# CDTV-adaptor-ATX_1_1.net
KiCad netlist of a schematic drawn in EAGLE
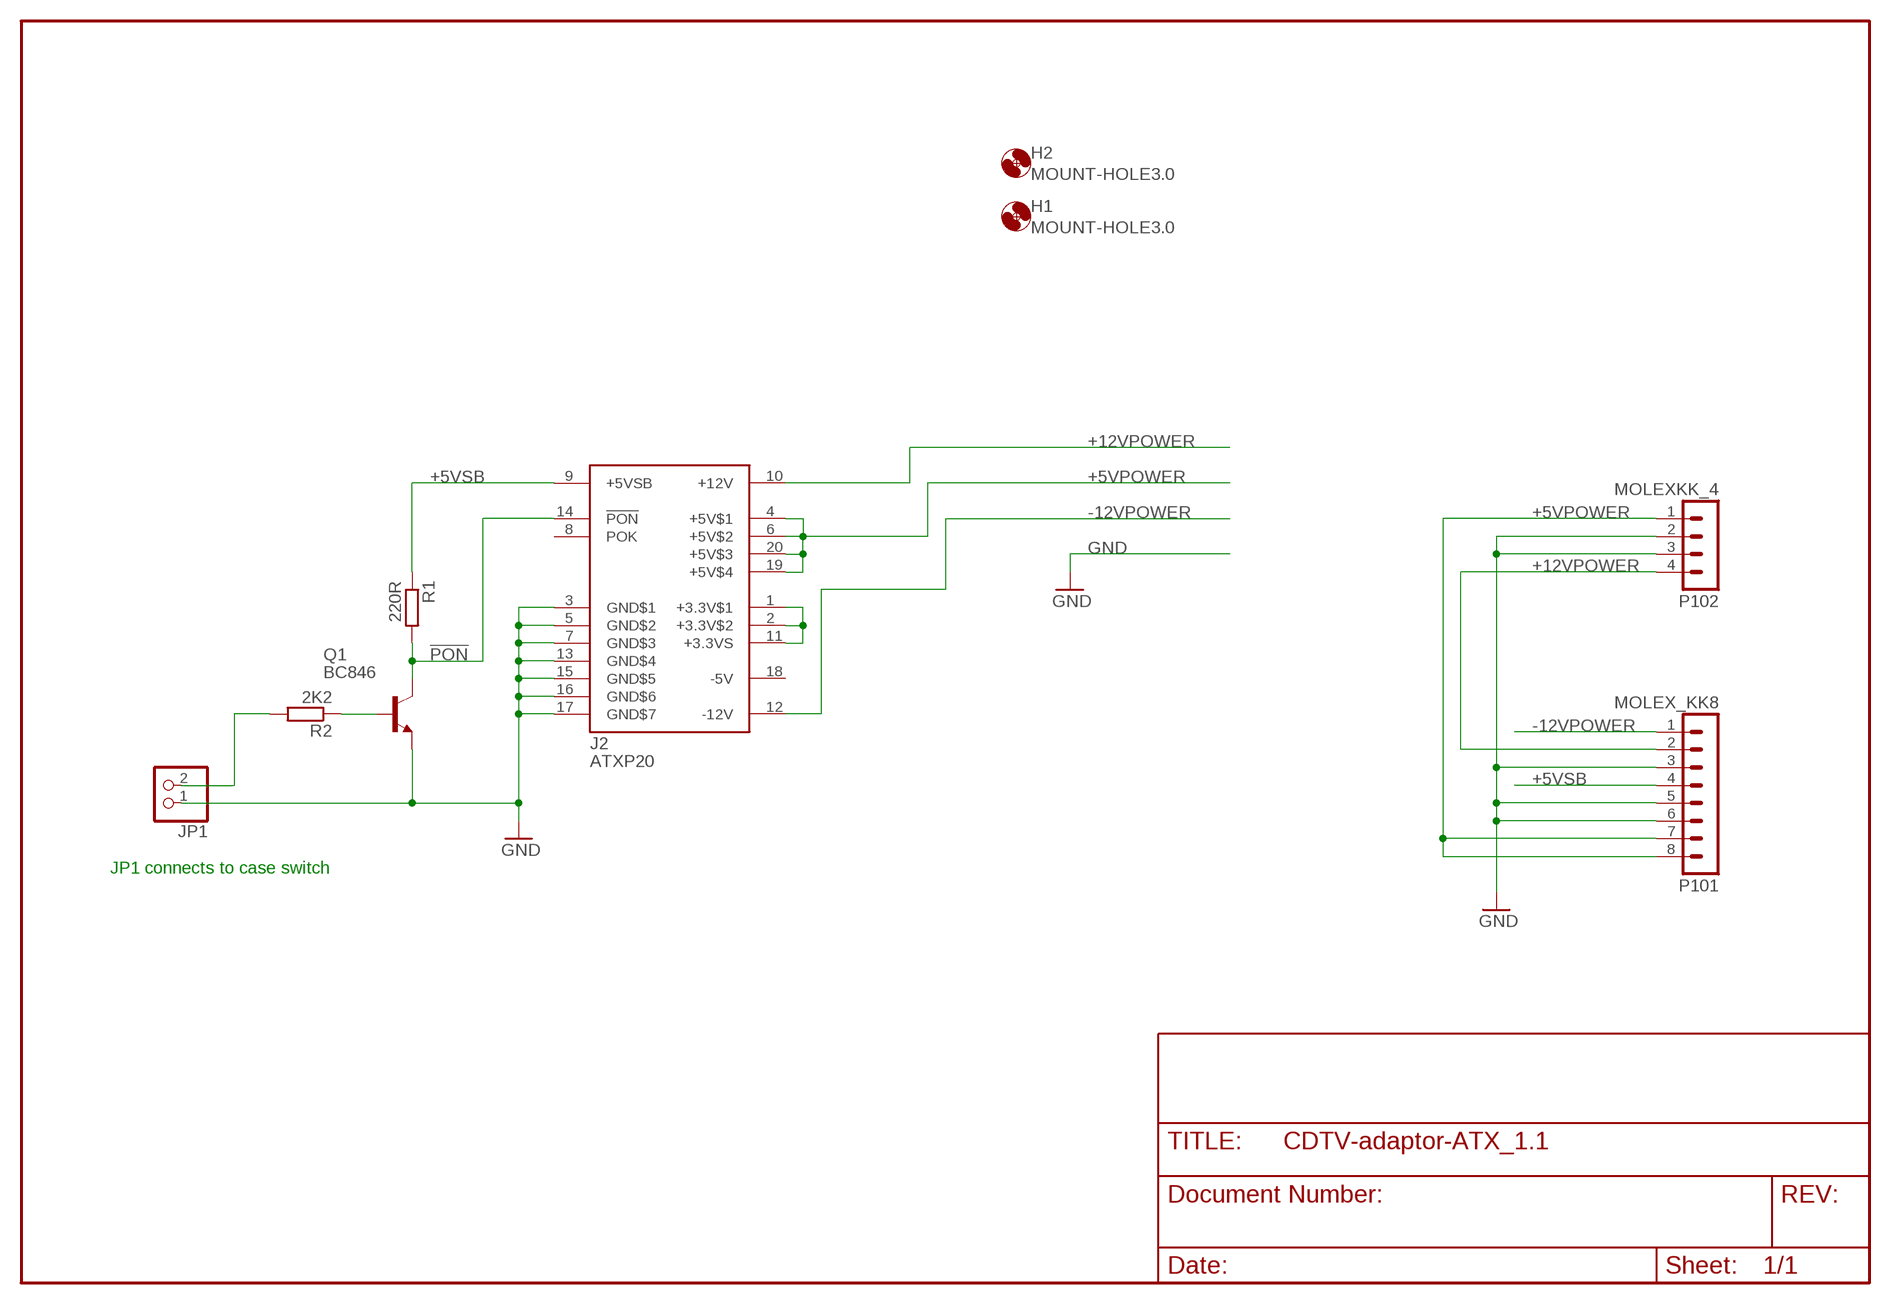
[diagram p0: schematic, sheet 1]

(export (version "E")
  (design (tool "Eeschema 10.0.6"))
  (components
    (comp (ref "H1")
      (value "MOUNT-HOLE3.0")
      (footprint "eagle-import:3,0")
      (libsource (lib "eagle-import") (part "MOUNT-HOLE3.0"))
    )
    (comp (ref "H2")
      (value "MOUNT-HOLE3.0")
      (footprint "eagle-import:3,0")
      (libsource (lib "eagle-import") (part "MOUNT-HOLE3.0"))
    )
    (comp (ref "J2")
      (value "ATXP20")
      (footprint "eagle-import:MOLEX39281203")
      (libsource (lib "eagle-import") (part "ATXP20"))
    )
    (comp (ref "JP1")
      (value "PINHD-1X2")
      (footprint "eagle-import:1X02")
      (libsource (lib "eagle-import") (part "PINHD-1X2"))
    )
    (comp (ref "P101")
      (value "MOLEX_KK8")
      (footprint "eagle-import:MOLEX_KK8")
      (libsource (lib "eagle-import") (part "MOLEX_KK8"))
    )
    (comp (ref "P102")
      (value "MOLEXKK_4")
      (footprint "eagle-import:MA04-1")
      (libsource (lib "eagle-import") (part "MOLEXKK_4"))
    )
    (comp (ref "Q1")
      (value "BC846")
      (footprint "eagle-import:SOT23")
      (libsource (lib "eagle-import") (part "BC846"))
    )
    (comp (ref "R1")
      (value "220R")
      (footprint "eagle-import:R0603")
      (libsource (lib "eagle-import") (part "R-EU_R0603"))
    )
    (comp (ref "R2")
      (value "2K2")
      (footprint "eagle-import:R0603")
      (libsource (lib "eagle-import") (part "R-EU_R0603"))
    )
  )
  (nets
    (net (code "1") (name "/+5VPOWER") (class "Default")
      (node (ref "J2") (pin "19") (pinfunction "+5V$4_19") (pintype "power_in"))
      (node (ref "J2") (pin "20") (pinfunction "+5V$3_20") (pintype "power_in"))
      (node (ref "J2") (pin "4") (pinfunction "+5V$1_4") (pintype "power_in"))
      (node (ref "J2") (pin "6") (pinfunction "+5V$2_6") (pintype "power_in"))
      (node (ref "P101") (pin "7") (pinfunction "7_7") (pintype "passive"))
      (node (ref "P101") (pin "8") (pinfunction "8_8") (pintype "passive"))
      (node (ref "P102") (pin "1") (pinfunction "1_1") (pintype "passive"))
    )
    (net (code "2") (name "/+5VSB") (class "Default")
      (node (ref "J2") (pin "9") (pinfunction "+5VSB_9") (pintype "power_in"))
      (node (ref "P101") (pin "4") (pinfunction "4_4") (pintype "passive"))
      (node (ref "R1") (pin "1") (pinfunction "1_1") (pintype "passive"))
    )
    (net (code "3") (name "/+12VPOWER") (class "Default")
      (node (ref "J2") (pin "10") (pinfunction "+12V_10") (pintype "power_in"))
      (node (ref "P101") (pin "2") (pinfunction "2_2") (pintype "passive"))
      (node (ref "P102") (pin "4") (pinfunction "4_4") (pintype "passive"))
    )
    (net (code "4") (name "/-5V") (class "Default")
      (node (ref "J2") (pin "18") (pinfunction "-5V_18") (pintype "power_in"))
    )
    (net (code "5") (name "/-12VPOWER") (class "Default")
      (node (ref "J2") (pin "12") (pinfunction "-12V_12") (pintype "power_in"))
      (node (ref "P101") (pin "1") (pinfunction "1_1") (pintype "passive"))
    )
    (net (code "6") (name "/~{PON}") (class "Default")
      (node (ref "J2") (pin "14") (pinfunction "~{PON}_14") (pintype "input"))
      (node (ref "Q1") (pin "3") (pinfunction "C_3") (pintype "passive"))
      (node (ref "R1") (pin "2") (pinfunction "2_2") (pintype "passive"))
    )
    (net (code "7") (name "GND") (class "Default")
      (node (ref "J2") (pin "13") (pinfunction "GND$4_13") (pintype "power_in"))
      (node (ref "J2") (pin "15") (pinfunction "GND$5_15") (pintype "power_in"))
      (node (ref "J2") (pin "16") (pinfunction "GND$6_16") (pintype "power_in"))
      (node (ref "J2") (pin "17") (pinfunction "GND$7_17") (pintype "power_in"))
      (node (ref "J2") (pin "3") (pinfunction "GND$1_3") (pintype "power_in"))
      (node (ref "J2") (pin "5") (pinfunction "GND$2_5") (pintype "power_in"))
      (node (ref "J2") (pin "7") (pinfunction "GND$3_7") (pintype "power_in"))
      (node (ref "JP1") (pin "1") (pinfunction "1_1") (pintype "passive"))
      (node (ref "P101") (pin "3") (pinfunction "3_3") (pintype "passive"))
      (node (ref "P101") (pin "5") (pinfunction "5_5") (pintype "passive"))
      (node (ref "P101") (pin "6") (pinfunction "6_6") (pintype "passive"))
      (node (ref "P102") (pin "2") (pinfunction "2_2") (pintype "passive"))
      (node (ref "P102") (pin "3") (pinfunction "3_3") (pintype "passive"))
      (node (ref "Q1") (pin "2") (pinfunction "E_2") (pintype "passive"))
    )
    (net (code "8") (name "Net-(J2-+3.3V$1)") (class "Default")
      (node (ref "J2") (pin "1") (pinfunction "+3.3V$1_1") (pintype "power_in"))
      (node (ref "J2") (pin "11") (pinfunction "+3.3VS_11") (pintype "power_in"))
      (node (ref "J2") (pin "2") (pinfunction "+3.3V$2_2") (pintype "power_in"))
    )
    (net (code "9") (name "Net-(JP1-Pad2)") (class "Default")
      (node (ref "JP1") (pin "2") (pinfunction "2_2") (pintype "passive"))
      (node (ref "R2") (pin "2") (pinfunction "2_2") (pintype "passive"))
    )
    (net (code "10") (name "Net-(Q1-B)") (class "Default")
      (node (ref "Q1") (pin "1") (pinfunction "B_1") (pintype "passive"))
      (node (ref "R2") (pin "1") (pinfunction "1_1") (pintype "passive"))
    )
    (net (code "11") (name "unconnected-(J2-POK-Pad8)") (class "Default")
      (node (ref "J2") (pin "8") (pinfunction "POK_8") (pintype "output"))
    )
  )
)
